# v1.net
KiCad netlist of a schematic drawn in EAGLE
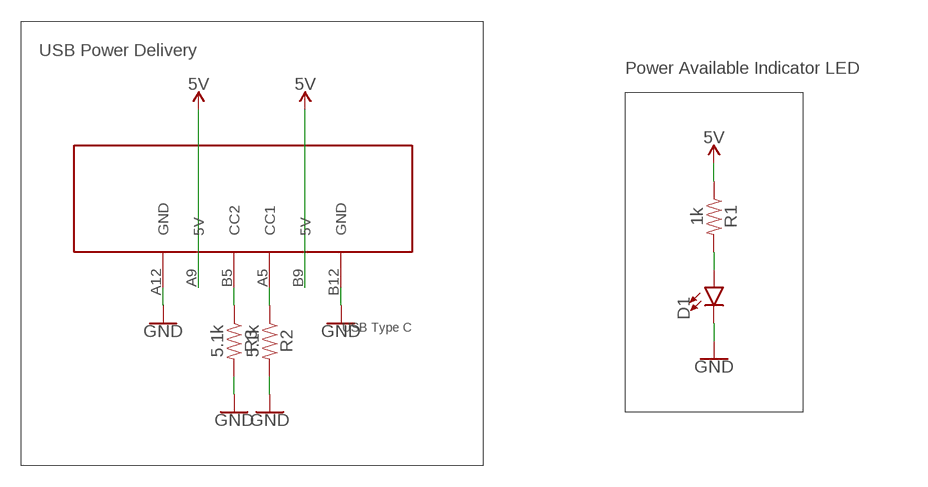
[diagram p0: schematic, sheet 1]

(export (version "E")
  (design (tool "Eeschema 10.0.6"))
  (components
    (comp (ref "D1")
      (value "LED1206")
      (footprint "eagle-import:LED-1206")
      (libsource (lib "eagle-import") (part "LED1206"))
    )
    (comp (ref "R1")
      (value "1k")
      (footprint "eagle-import:0805")
      (libsource (lib "eagle-import") (part "0.75OHM-0805-1/4W-1%"))
    )
    (comp (ref "R2")
      (value "5.1k")
      (footprint "eagle-import:0805")
      (libsource (lib "eagle-import") (part "0.75OHM-0805-1/4W-1%"))
    )
    (comp (ref "R3")
      (value "5.1k")
      (footprint "eagle-import:0805")
      (libsource (lib "eagle-import") (part "0.75OHM-0805-1/4W-1%"))
    )
    (comp (ref "U$1")
      (value "USBC6PIN")
      (footprint "eagle-import:USBC6PIN")
      (libsource (lib "eagle-import") (part "USBC6PIN"))
    )
  )
  (nets
    (net (code "1") (name "5V") (class "Default")
      (node (ref "R1") (pin "1") (pinfunction "1_1") (pintype "passive"))
      (node (ref "U$1") (pin "A9") (pinfunction "5V_A9") (pintype "bidirectional"))
      (node (ref "U$1") (pin "B9") (pinfunction "5V_B9") (pintype "bidirectional"))
    )
    (net (code "2") (name "GND") (class "Default")
      (node (ref "D1") (pin "C") (pinfunction "C_C") (pintype "passive"))
      (node (ref "R2") (pin "2") (pinfunction "2_2") (pintype "passive"))
      (node (ref "R3") (pin "2") (pinfunction "2_2") (pintype "passive"))
      (node (ref "U$1") (pin "A12") (pinfunction "GND_A12") (pintype "bidirectional"))
      (node (ref "U$1") (pin "B12") (pinfunction "GND_B12") (pintype "bidirectional"))
    )
    (net (code "3") (name "Net-(D1-PadA)") (class "Default")
      (node (ref "D1") (pin "A") (pinfunction "A_A") (pintype "passive"))
      (node (ref "R1") (pin "2") (pinfunction "2_2") (pintype "passive"))
    )
    (net (code "4") (name "Net-(U$1-CC1)") (class "Default")
      (node (ref "R2") (pin "1") (pinfunction "1_1") (pintype "passive"))
      (node (ref "U$1") (pin "A5") (pinfunction "CC1_A5") (pintype "bidirectional"))
    )
    (net (code "5") (name "Net-(U$1-CC2)") (class "Default")
      (node (ref "R3") (pin "1") (pinfunction "1_1") (pintype "passive"))
      (node (ref "U$1") (pin "B5") (pinfunction "CC2_B5") (pintype "bidirectional"))
    )
  )
)
